# Powerboard_Rev01.net
KiCad netlist of a schematic drawn in Altium Designer
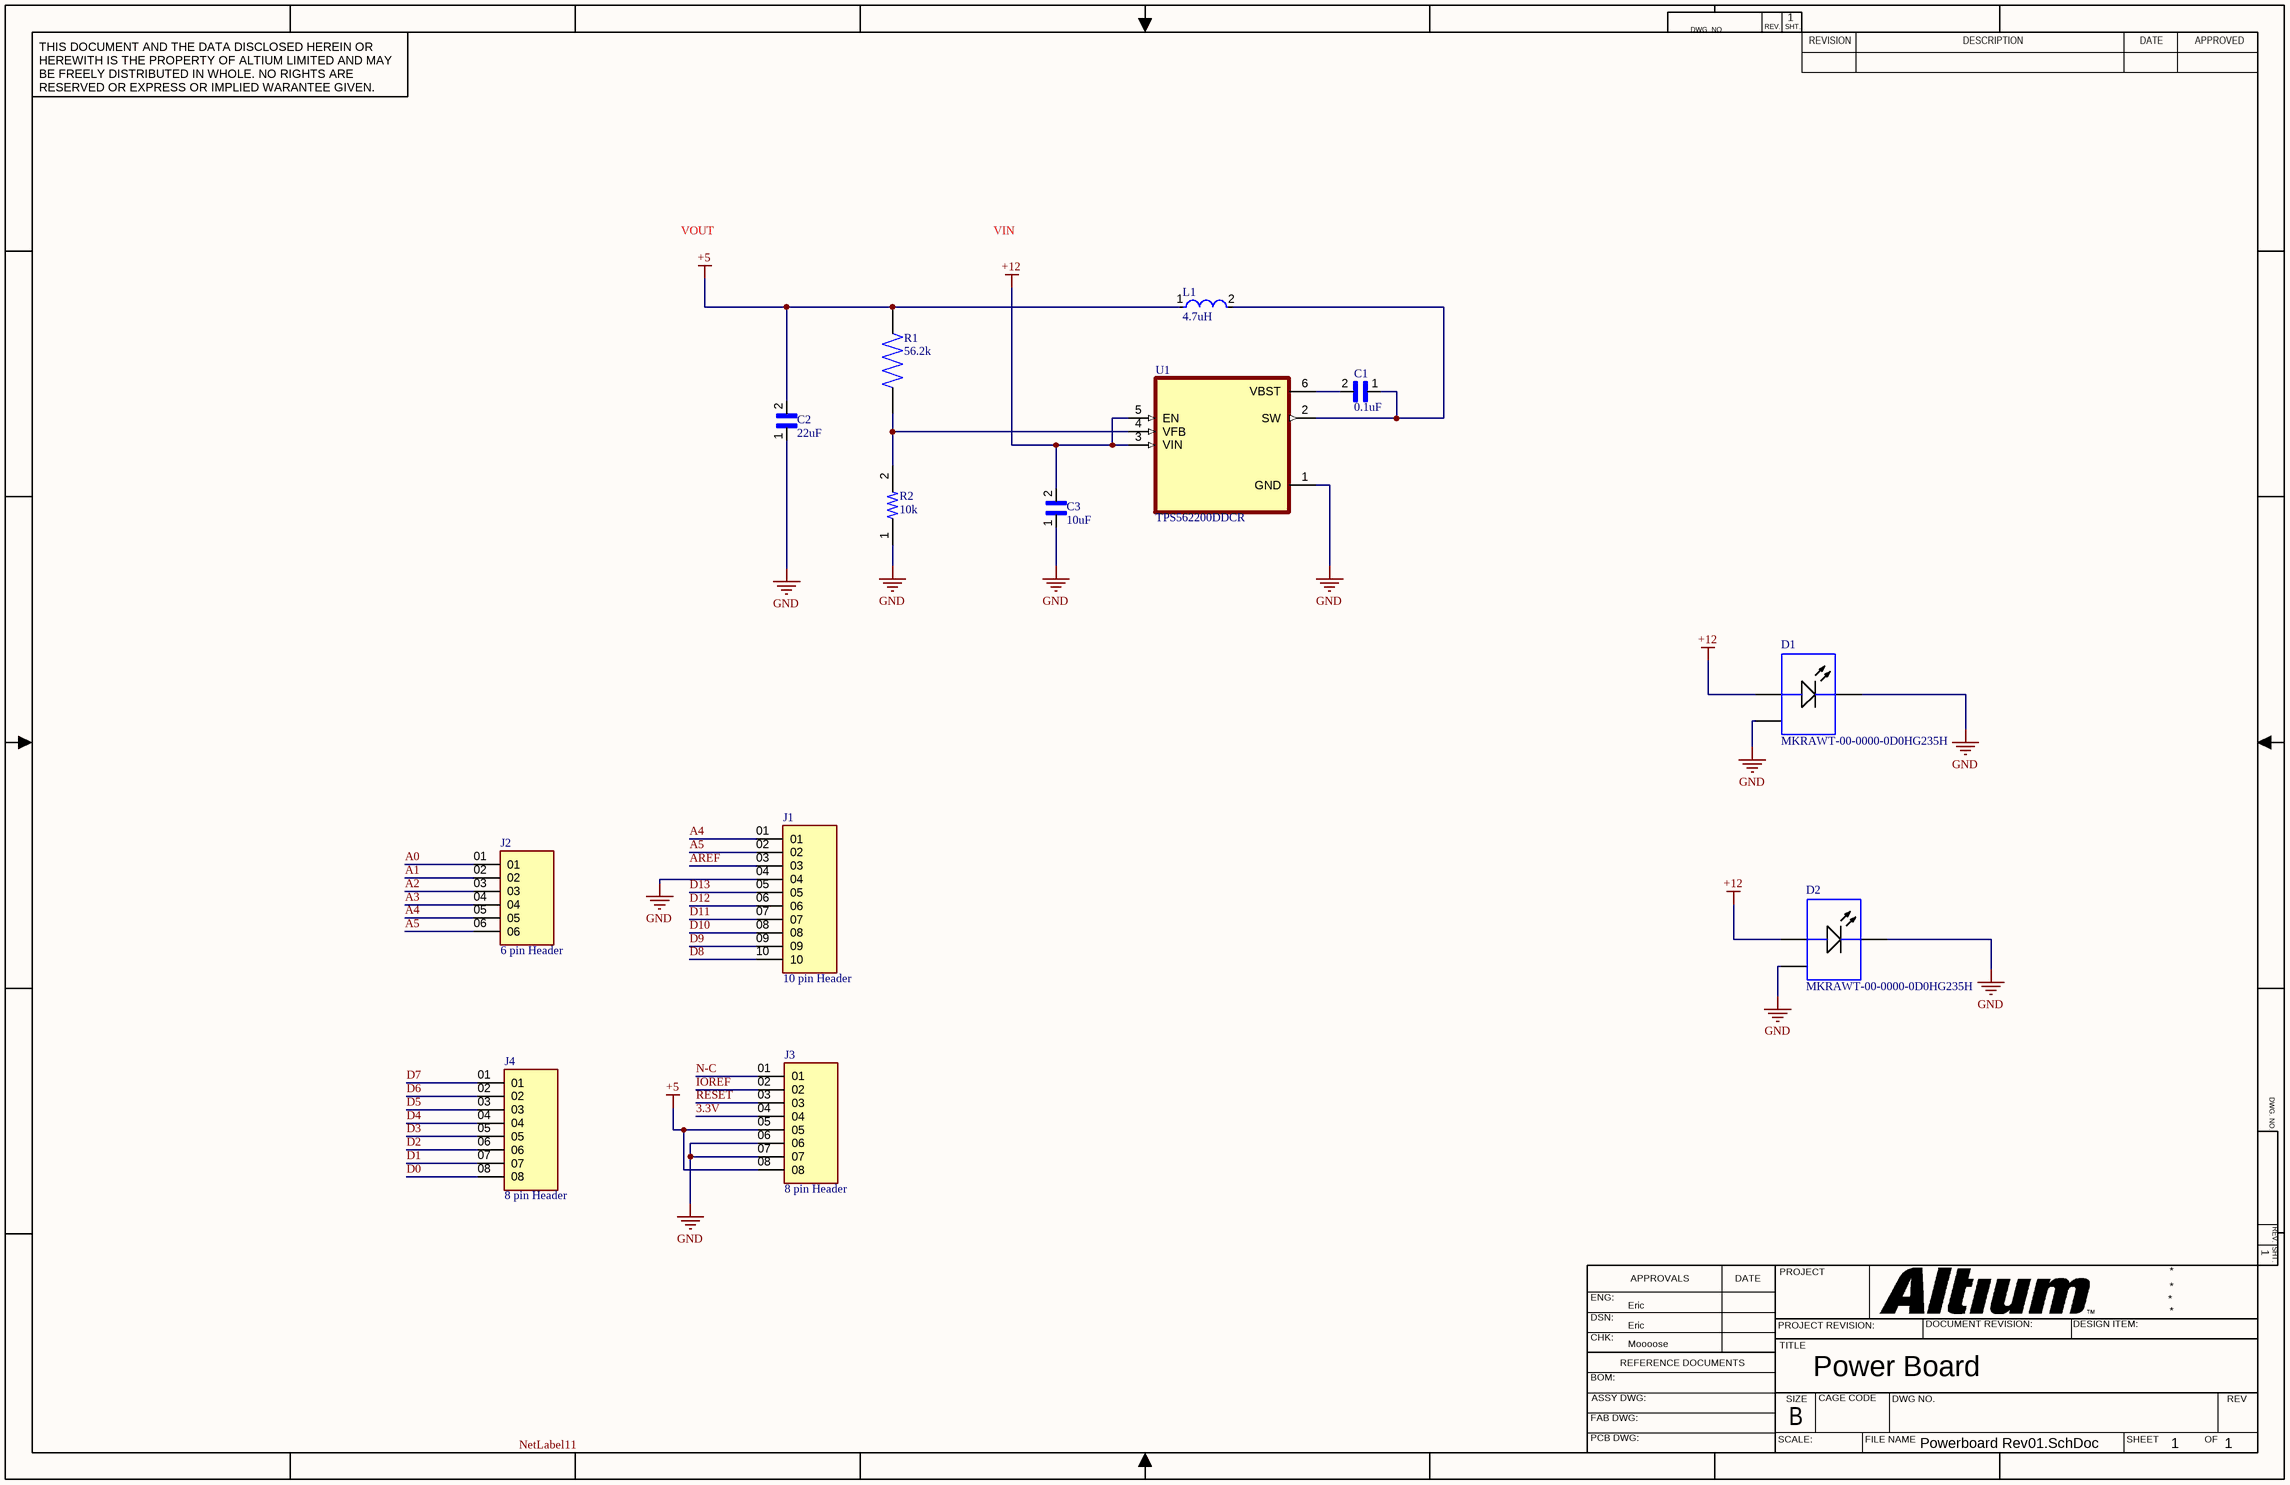
[diagram p0: Powerboard Rev01.SchDoc]

(export (version "E")
  (design (tool "Eeschema 10.0.6"))
  (components
    (comp (ref "C1")
      (value "0.1uF")
      (footprint "08053C-104KAT2A:CAPC2012X94N")
      (description "08053C104KAT2A Cap Ceramic 0.1uF 25V X7R 10% Pad SMD 0805 125ÂÂŽ T/R")
      (fields
        (field (name "MP") "08053C104KAT2A")
        (field (name "MF") "{'manufacturer': u'AVX Interconnect / Elco'}")
      )
      (libsource (lib "*") (part "08053C104KAT2A"))
    )
    (comp (ref "C2")
      (value "22uF")
      (footprint "C1608X5R1A226M080AC:CAPC1608X100N")
      (description "C1608X5R1A226M080AC 22µF ±20% 10V Ceramic Capacitor X5R 0603 (1608 Metric)")
      (fields (field (name "MF") "{'manufacturer': u'TDK'}") (field (name "MP") "C1608X5R1A226M080AC"))
      (libsource (lib "*") (part "C1608X5R1A226M080AC"))
    )
    (comp (ref "C3")
      (value "10uF")
      (footprint "C2012X5R1V106K085AC:CAPC2012X100N")
      (description "C2012X5R1V106K085AC 10µF ±10% 35V Ceramic Capacitor X5R 0805 (2012 Metric)")
      (fields (field (name "MF") "{'manufacturer': u'TDK'}") (field (name "MP") "C2012X5R1V106K085AC"))
      (libsource (lib "*") (part "C2012X5R1V106K085AC"))
    )
    (comp (ref "D1")
      (value "MKRAWT-00-0000-0D0HG235H")
      (footprint "CREE-MK-R-2_V")
      (description "LED, White, 12 V, 2-Pin SMD, RoHS, Tape and Reel")
      (libsource (lib "Altium Content Vault") (part "LED_WHITE-3"))
    )
    (comp (ref "D2")
      (value "MKRAWT-00-0000-0D0HG235H")
      (footprint "CREE-MK-R-2_V")
      (description "LED, White, 12 V, 2-Pin SMD, RoHS, Tape and Reel")
      (libsource (lib "Altium Content Vault") (part "LED_WHITE-3"))
    )
    (comp (ref "J1")
      (value "10 pin Header")
      (footprint "SSQ-110-03-T-S:SAMTEC_SSQ-110-03-X-S")
      (description "SSQ-110-03-X-S 10 Position Receptacle Connector Through Hole")
      (fields (field (name "MP") "SSQ-110-03-X-S") (field (name "MF") "{'manufacturer': u'Samtec'}"))
      (libsource (lib "*") (part "SSQ-110-03-X-S"))
    )
    (comp (ref "J2")
      (value "6 pin Header")
      (footprint "SSQ-106-03-T-S:SAMTEC_SSQ-106-03-X-S")
      (description "SSQ-106-03-X-S 6 Position Receptacle Connector Through Hole")
      (fields (field (name "MF") "{'manufacturer': u'Samtec Inc.'}") (field (name "MP") "SSQ-106-03-X-S"))
      (libsource (lib "*") (part "SSQ-106-03-X-S"))
    )
    (comp (ref "J3")
      (value "8 pin Header")
      (footprint "SSQ-108-03-T-S:SAMTEC_SSQ-108-03-X-S")
      (description "SSQ-108-03-X-S")
      (fields (field (name "MF") "{'manufacturer': u'Samtec'}"))
      (libsource (lib "*") (part "SSQ-108-03-X-S"))
    )
    (comp (ref "J4")
      (value "8 pin Header")
      (footprint "SSQ-108-03-T-S:SAMTEC_SSQ-108-03-X-S")
      (description "SSQ-108-03-X-S")
      (fields (field (name "MF") "{'manufacturer': u'Samtec'}"))
      (libsource (lib "*") (part "SSQ-108-03-X-S"))
    )
    (comp (ref "L1")
      (value "4.7uH")
      (footprint "FP-NR5040-H_4_1-MFG")
      (description "NR5040T4R7N SMD Power Inductors 4.7uH ±30% 3.1A 37.7mΩ")
      (fields (field (name "TOLERANCE") "30%"))
      (libsource (lib "Altium Content Vault") (part "725321dda6339637d4d059423bc1c3c"))
    )
    (comp (ref "R1")
      (value "56.2k")
      (footprint "RC0201FR-0756K2L:RESC0603X26N")
      (description "RC0201FR-0756K2L RES SMD 56.2K OHM 1% 1/20W 0201")
      (fields (field (name "MP") "RC0201FR-0756K2L") (field (name "MF") "{'manufacturer': u'Yageo'}"))
      (libsource (lib "*") (part "RC0201FR-0756K2L"))
    )
    (comp (ref "R2")
      (value "10k")
      (footprint "RC0201FR-0710KL:RESC0603X26N")
      (description "RC0201FR-0710KL  10.0K 1% 0.05W TK200")
      (fields (field (name "MP") "RC0201FR-0710KL") (field (name "MF") "{'manufacturer': u'Yageo'}"))
      (libsource (lib "*") (part "RC0201FR-0710KL"))
    )
    (comp (ref "U1")
      (value "TPS562200DDCR")
      (footprint "TPS562200DDCR:SOT95P280X110-6N")
      (fields (field (name "MF") "{'manufacturer': u'Texas Instruments'}"))
      (libsource (lib "*") (part "TPS562200DDCR"))
    )
  )
  (nets
    (net (code "1") (name "+5") (class "Default")
      (node (ref "C2") (pin "2") (pinfunction "2_2") (pintype "passive"))
      (node (ref "J3") (pin "05") (pinfunction "05_05") (pintype "passive"))
      (node (ref "J3") (pin "08") (pinfunction "08_08") (pintype "passive"))
      (node (ref "L1") (pin "1") (pinfunction "1_1") (pintype "passive"))
      (node (ref "R1") (pin "2") (pinfunction "2_2") (pintype "passive"))
    )
    (net (code "2") (name "+12") (class "Default")
      (node (ref "C3") (pin "2") (pinfunction "2_2") (pintype "passive"))
      (node (ref "D1") (pin "1") (pinfunction "A_1") (pintype "passive"))
      (node (ref "D2") (pin "1") (pinfunction "A_1") (pintype "passive"))
      (node (ref "U1") (pin "3") (pinfunction "VIN_3") (pintype "input"))
      (node (ref "U1") (pin "5") (pinfunction "EN_5") (pintype "input"))
    )
    (net (code "3") (name "/3.3V") (class "Default")
      (node (ref "J3") (pin "04") (pinfunction "04_04") (pintype "passive"))
    )
    (net (code "4") (name "/A0") (class "Default")
      (node (ref "J2") (pin "01") (pinfunction "01_01") (pintype "passive"))
    )
    (net (code "5") (name "/A1") (class "Default")
      (node (ref "J2") (pin "02") (pinfunction "02_02") (pintype "passive"))
    )
    (net (code "6") (name "/A2") (class "Default")
      (node (ref "J2") (pin "03") (pinfunction "03_03") (pintype "passive"))
    )
    (net (code "7") (name "/A3") (class "Default")
      (node (ref "J2") (pin "04") (pinfunction "04_04") (pintype "passive"))
    )
    (net (code "8") (name "/A4") (class "Default")
      (node (ref "J1") (pin "01") (pinfunction "01_01") (pintype "passive"))
      (node (ref "J2") (pin "05") (pinfunction "05_05") (pintype "passive"))
    )
    (net (code "9") (name "/A5") (class "Default")
      (node (ref "J1") (pin "02") (pinfunction "02_02") (pintype "passive"))
      (node (ref "J2") (pin "06") (pinfunction "06_06") (pintype "passive"))
    )
    (net (code "10") (name "/AREF") (class "Default")
      (node (ref "J1") (pin "03") (pinfunction "03_03") (pintype "passive"))
    )
    (net (code "11") (name "/D0") (class "Default")
      (node (ref "J4") (pin "08") (pinfunction "08_08") (pintype "passive"))
    )
    (net (code "12") (name "/D1") (class "Default")
      (node (ref "J4") (pin "07") (pinfunction "07_07") (pintype "passive"))
    )
    (net (code "13") (name "/D2") (class "Default")
      (node (ref "J4") (pin "06") (pinfunction "06_06") (pintype "passive"))
    )
    (net (code "14") (name "/D3") (class "Default")
      (node (ref "J4") (pin "05") (pinfunction "05_05") (pintype "passive"))
    )
    (net (code "15") (name "/D4") (class "Default")
      (node (ref "J4") (pin "04") (pinfunction "04_04") (pintype "passive"))
    )
    (net (code "16") (name "/D5") (class "Default")
      (node (ref "J4") (pin "03") (pinfunction "03_03") (pintype "passive"))
    )
    (net (code "17") (name "/D6") (class "Default")
      (node (ref "J4") (pin "02") (pinfunction "02_02") (pintype "passive"))
    )
    (net (code "18") (name "/D7") (class "Default")
      (node (ref "J4") (pin "01") (pinfunction "01_01") (pintype "passive"))
    )
    (net (code "19") (name "/D8") (class "Default")
      (node (ref "J1") (pin "10") (pinfunction "10_10") (pintype "passive"))
    )
    (net (code "20") (name "/D9") (class "Default")
      (node (ref "J1") (pin "09") (pinfunction "09_09") (pintype "passive"))
    )
    (net (code "21") (name "/D10") (class "Default")
      (node (ref "J1") (pin "08") (pinfunction "08_08") (pintype "passive"))
    )
    (net (code "22") (name "/D11") (class "Default")
      (node (ref "J1") (pin "07") (pinfunction "07_07") (pintype "passive"))
    )
    (net (code "23") (name "/D12") (class "Default")
      (node (ref "J1") (pin "06") (pinfunction "06_06") (pintype "passive"))
    )
    (net (code "24") (name "/D13") (class "Default")
      (node (ref "J1") (pin "05") (pinfunction "05_05") (pintype "passive"))
    )
    (net (code "25") (name "/IOREF") (class "Default")
      (node (ref "J3") (pin "02") (pinfunction "02_02") (pintype "passive"))
    )
    (net (code "26") (name "/N-C") (class "Default")
      (node (ref "J3") (pin "01") (pinfunction "01_01") (pintype "passive"))
    )
    (net (code "28") (name "/RESET") (class "Default")
      (node (ref "J3") (pin "03") (pinfunction "03_03") (pintype "passive"))
    )
    (net (code "29") (name "GND") (class "Default")
      (node (ref "C2") (pin "1") (pinfunction "1_1") (pintype "passive"))
      (node (ref "C3") (pin "1") (pinfunction "1_1") (pintype "passive"))
      (node (ref "D1") (pin "2") (pinfunction "K_2") (pintype "passive"))
      (node (ref "D1") (pin "3") (pinfunction "EP_3") (pintype "passive"))
      (node (ref "D2") (pin "2") (pinfunction "K_2") (pintype "passive"))
      (node (ref "D2") (pin "3") (pinfunction "EP_3") (pintype "passive"))
      (node (ref "J1") (pin "04") (pinfunction "04_04") (pintype "passive"))
      (node (ref "J3") (pin "06") (pinfunction "06_06") (pintype "passive"))
      (node (ref "J3") (pin "07") (pinfunction "07_07") (pintype "passive"))
      (node (ref "R2") (pin "1") (pinfunction "1_1") (pintype "passive"))
      (node (ref "U1") (pin "1") (pinfunction "GND_1") (pintype "power_in"))
    )
    (net (code "30") (name "Net-(U1-SW)") (class "Default")
      (node (ref "C1") (pin "1") (pinfunction "1_1") (pintype "passive"))
      (node (ref "L1") (pin "2") (pinfunction "2_2") (pintype "passive"))
      (node (ref "U1") (pin "2") (pinfunction "SW_2") (pintype "output"))
    )
    (net (code "31") (name "Net-(U1-VBST)") (class "Default")
      (node (ref "C1") (pin "2") (pinfunction "2_2") (pintype "passive"))
      (node (ref "U1") (pin "6") (pinfunction "VBST_6") (pintype "power_in"))
    )
    (net (code "32") (name "Net-(U1-VFB)") (class "Default")
      (node (ref "R1") (pin "1") (pinfunction "1_1") (pintype "passive"))
      (node (ref "R2") (pin "2") (pinfunction "2_2") (pintype "passive"))
      (node (ref "U1") (pin "4") (pinfunction "VFB_4") (pintype "input"))
    )
  )
)
